# attiny85.net
KiCad netlist of a schematic drawn in EAGLE
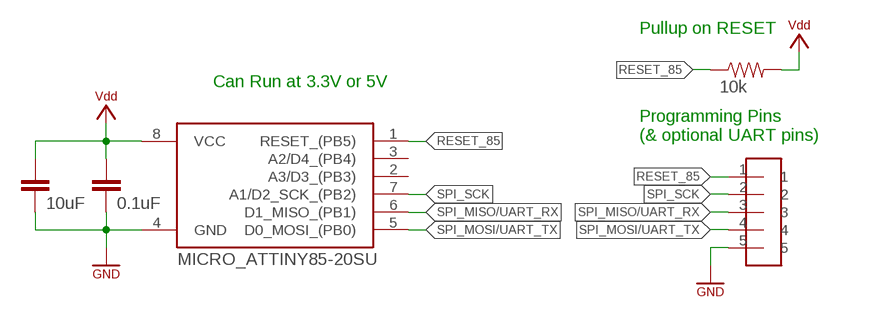
[diagram p0: schematic, sheet 1]

(export (version "E")
  (design (tool "Eeschema 10.0.6"))
  (components
    (comp (ref "C1")
      (value "0.1uF")
      (footprint "eagle-import:0805")
      (libsource (lib "eagle-import") (part "COMPONENT_CAP-0805"))
    )
    (comp (ref "C2")
      (value "10uF")
      (footprint "eagle-import:0805")
      (libsource (lib "eagle-import") (part "COMPONENT_CAP-0805"))
    )
    (comp (ref "R1")
      (value "10k")
      (footprint "eagle-import:0805")
      (libsource (lib "eagle-import") (part "COMPONENT_RESISTOR-0805"))
    )
    (comp (ref "U$1")
      (value "MICRO_ATTINY85-20SU")
      (footprint "eagle-import:SOIC8")
      (libsource (lib "eagle-import") (part "MICRO_ATTINY85-20SU"))
    )
    (comp (ref "U$2")
      (value "HEADER-5-TESTPOINT")
      (footprint "eagle-import:TESTPOINT-5")
      (libsource (lib "eagle-import") (part "HEADER-5-TESTPOINT"))
    )
  )
  (nets
    (net (code "1") (name "RESET_85") (class "Default")
      (node (ref "R1") (pin "1") (pinfunction "1_1") (pintype "passive"))
      (node (ref "U$1") (pin "1") (pinfunction "RESET_(PB5)_1") (pintype "bidirectional"))
      (node (ref "U$2") (pin "1") (pinfunction "1_1") (pintype "bidirectional"))
    )
    (net (code "2") (name "SPI_MISO{slash}UART_RX") (class "Default")
      (node (ref "U$1") (pin "6") (pinfunction "D1_MISO_(PB1)_6") (pintype "bidirectional"))
      (node (ref "U$2") (pin "3") (pinfunction "3_3") (pintype "bidirectional"))
    )
    (net (code "3") (name "SPI_MOSI{slash}UART_TX") (class "Default")
      (node (ref "U$1") (pin "5") (pinfunction "D0_MOSI_(PB0)_5") (pintype "bidirectional"))
      (node (ref "U$2") (pin "4") (pinfunction "4_4") (pintype "bidirectional"))
    )
    (net (code "4") (name "SPI_SCK") (class "Default")
      (node (ref "U$1") (pin "7") (pinfunction "A1/D2_SCK_(PB2)_7") (pintype "bidirectional"))
      (node (ref "U$2") (pin "2") (pinfunction "2_2") (pintype "bidirectional"))
    )
    (net (code "5") (name "SYMBOL_GND") (class "Default")
      (node (ref "C1") (pin "2") (pinfunction "2_2") (pintype "passive"))
      (node (ref "C2") (pin "2") (pinfunction "2_2") (pintype "passive"))
      (node (ref "U$1") (pin "4") (pinfunction "GND_4") (pintype "power_in"))
      (node (ref "U$2") (pin "5") (pinfunction "5_5") (pintype "bidirectional"))
    )
    (net (code "6") (name "SYMBOL_VDD") (class "Default")
      (node (ref "C1") (pin "1") (pinfunction "1_1") (pintype "passive"))
      (node (ref "C2") (pin "1") (pinfunction "1_1") (pintype "passive"))
      (node (ref "R1") (pin "2") (pinfunction "2_2") (pintype "passive"))
      (node (ref "U$1") (pin "8") (pinfunction "VCC_8") (pintype "power_in"))
    )
    (net (code "7") (name "unconnected-(U$1-A2{slash}D4_(PB4)-Pad3)") (class "Default")
      (node (ref "U$1") (pin "3") (pinfunction "A2/D4_(PB4)_3") (pintype "bidirectional"))
    )
    (net (code "8") (name "unconnected-(U$1-A3{slash}D3_(PB3)-Pad2)") (class "Default")
      (node (ref "U$1") (pin "2") (pinfunction "A3/D3_(PB3)_2") (pintype "bidirectional"))
    )
  )
)
